# SCORCH.net
KiCad netlist of a schematic drawn in EAGLE
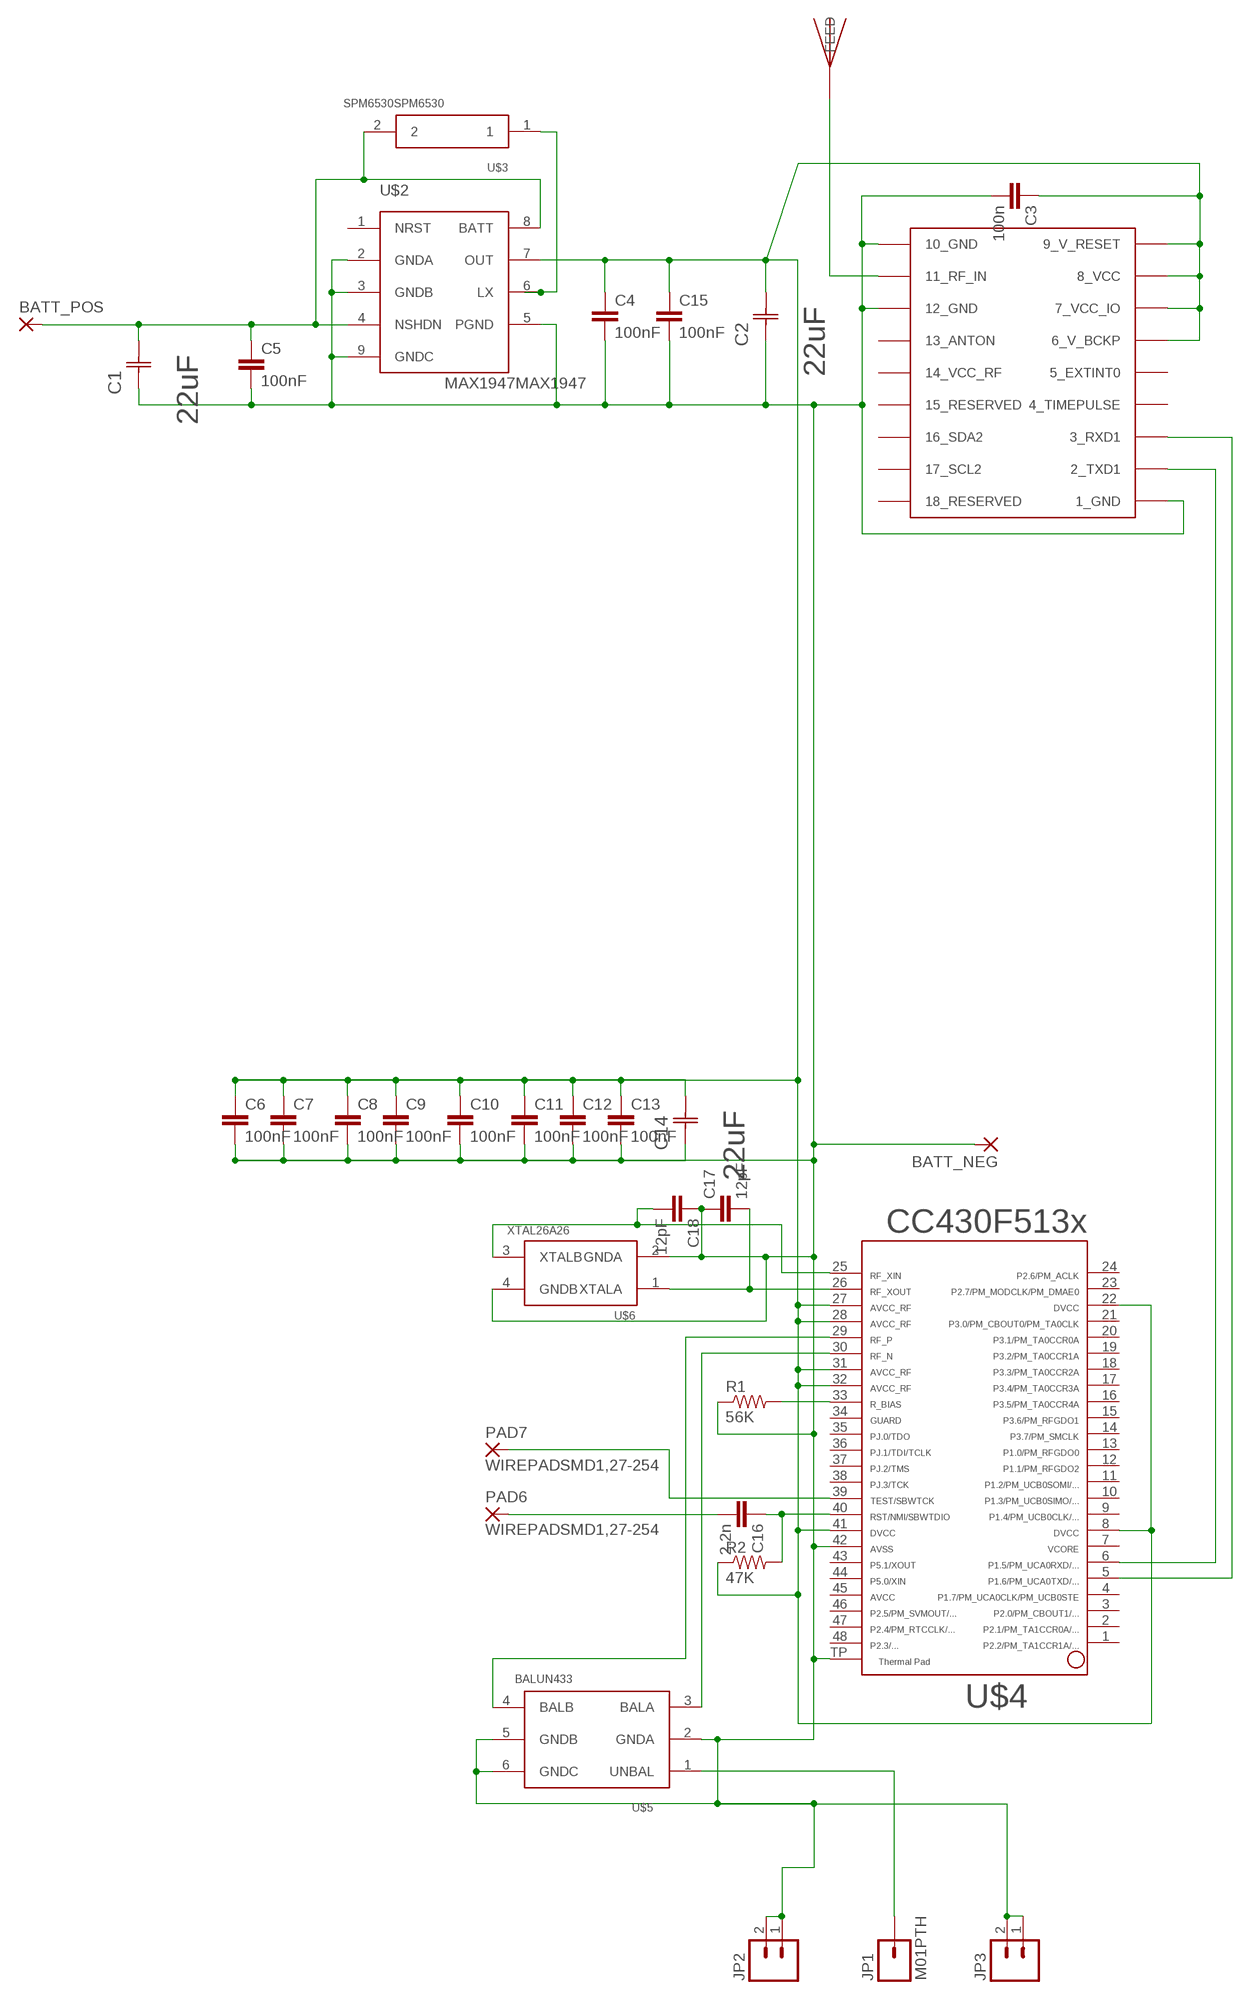
[diagram p0: schematic, sheet 1]

(export (version "E")
  (design (tool "Eeschema 10.0.6"))
  (components
    (comp (ref "BATT_NEG")
      (value "SMD2")
      (footprint "eagle-import:SMD1,27-2,54")
      (libsource (lib "eagle-import") (part "SMD2"))
    )
    (comp (ref "BATT_POS")
      (value "SMD2")
      (footprint "eagle-import:SMD1,27-2,54")
      (libsource (lib "eagle-import") (part "SMD2"))
    )
    (comp (ref "C1")
      (value "22uF")
      (footprint "eagle-import:CAPC2013X90N")
      (fields (field (name "MPN") "U0805R102KCT") (field (name "TOLERANCE") "±10%"))
      (libsource (lib "eagle-import") (part "U0805R102KCT"))
    )
    (comp (ref "C2")
      (value "22uF")
      (footprint "eagle-import:CAPC2013X90N")
      (fields (field (name "MPN") "U0805R102KCT") (field (name "TOLERANCE") "±10%"))
      (libsource (lib "eagle-import") (part "U0805R102KCT"))
    )
    (comp (ref "C3")
      (value "100n")
      (footprint "eagle-import:0402-CAP")
      (libsource (lib "eagle-import") (part "CAP0402-CAP"))
    )
    (comp (ref "C4")
      (value "100nF")
      (footprint "eagle-import:0402-CAP")
      (libsource (lib "eagle-import") (part "CAP0402-CAP"))
    )
    (comp (ref "C5")
      (value "100nF")
      (footprint "eagle-import:0402-CAP")
      (libsource (lib "eagle-import") (part "CAP0402-CAP"))
    )
    (comp (ref "C6")
      (value "100nF")
      (footprint "eagle-import:0402-CAP")
      (libsource (lib "eagle-import") (part "CAP0402-CAP"))
    )
    (comp (ref "C7")
      (value "100nF")
      (footprint "eagle-import:0402-CAP")
      (libsource (lib "eagle-import") (part "CAP0402-CAP"))
    )
    (comp (ref "C8")
      (value "100nF")
      (footprint "eagle-import:0402-CAP")
      (libsource (lib "eagle-import") (part "CAP0402-CAP"))
    )
    (comp (ref "C9")
      (value "100nF")
      (footprint "eagle-import:0402-CAP")
      (libsource (lib "eagle-import") (part "CAP0402-CAP"))
    )
    (comp (ref "C10")
      (value "100nF")
      (footprint "eagle-import:0402-CAP")
      (libsource (lib "eagle-import") (part "CAP0402-CAP"))
    )
    (comp (ref "C11")
      (value "100nF")
      (footprint "eagle-import:0402-CAP")
      (libsource (lib "eagle-import") (part "CAP0402-CAP"))
    )
    (comp (ref "C12")
      (value "100nF")
      (footprint "eagle-import:0402-CAP")
      (libsource (lib "eagle-import") (part "CAP0402-CAP"))
    )
    (comp (ref "C13")
      (value "100nF")
      (footprint "eagle-import:0402-CAP")
      (libsource (lib "eagle-import") (part "CAP0402-CAP"))
    )
    (comp (ref "C14")
      (value "22uF")
      (footprint "eagle-import:CAPC2013X90N")
      (fields (field (name "MPN") "U0805R102KCT") (field (name "TOLERANCE") "±10%"))
      (libsource (lib "eagle-import") (part "U0805R102KCT"))
    )
    (comp (ref "C15")
      (value "100nF")
      (footprint "eagle-import:0402-CAP")
      (libsource (lib "eagle-import") (part "CAP0402-CAP"))
    )
    (comp (ref "C16")
      (value "2.2n")
      (footprint "eagle-import:0402-CAP")
      (libsource (lib "eagle-import") (part "CAP0402-CAP"))
    )
    (comp (ref "C17")
      (value "12pF")
      (footprint "eagle-import:0402-CAP")
      (libsource (lib "eagle-import") (part "CAP0402-CAP"))
    )
    (comp (ref "C18")
      (value "12pF")
      (footprint "eagle-import:0402-CAP")
      (libsource (lib "eagle-import") (part "CAP0402-CAP"))
    )
    (comp (ref "JP1")
      (value "M01PTH")
      (footprint "eagle-import:1X01")
      (libsource (lib "eagle-import") (part "M01PTH"))
    )
    (comp (ref "JP2")
      (value "M02PTH")
      (footprint "eagle-import:1X02")
      (libsource (lib "eagle-import") (part "M02PTH"))
    )
    (comp (ref "JP3")
      (value "M02PTH")
      (footprint "eagle-import:1X02")
      (libsource (lib "eagle-import") (part "M02PTH"))
    )
    (comp (ref "PAD6")
      (value "WIREPADSMD1,27-254")
      (footprint "eagle-import:SMD1,27-2,54")
      (libsource (lib "eagle-import") (part "WIREPADSMD1,27-254"))
    )
    (comp (ref "PAD7")
      (value "WIREPADSMD1,27-254")
      (footprint "eagle-import:SMD1,27-2,54")
      (libsource (lib "eagle-import") (part "WIREPADSMD1,27-254"))
    )
    (comp (ref "R1")
      (value "56K")
      (footprint "eagle-import:0603-RES")
      (libsource (lib "eagle-import") (part "RESISTOR0603-RES"))
    )
    (comp (ref "R2")
      (value "47K")
      (footprint "eagle-import:0603-RES")
      (libsource (lib "eagle-import") (part "RESISTOR0603-RES"))
    )
    (comp (ref "U$1")
      (value "UBLOX_MAX-6")
      (footprint "eagle-import:UBLOX_MAX-6")
      (libsource (lib "eagle-import") (part "UBLOX_MAX-6"))
    )
    (comp (ref "U$2")
      (value "MAX1947MAX1947")
      (footprint "eagle-import:8QFN")
      (libsource (lib "eagle-import") (part "MAX1947MAX1947"))
    )
    (comp (ref "U$3")
      (value "SPM6530SPM6530")
      (footprint "eagle-import:INDUCTOR")
      (libsource (lib "eagle-import") (part "SPM6530SPM6530"))
    )
    (comp (ref "U$4")
      (value "CC430F513X---RGZ48")
      (footprint "eagle-import:RGZ48")
      (libsource (lib "eagle-import") (part "CC430F513X---RGZ48"))
    )
    (comp (ref "U$5")
      (value "BALUN433")
      (footprint "eagle-import:BALUN")
      (libsource (lib "eagle-import") (part "BALUN433"))
    )
    (comp (ref "U$6")
      (value "XTAL26A26")
      (footprint "eagle-import:XTAL26")
      (libsource (lib "eagle-import") (part "XTAL26A26"))
    )
    (comp (ref "U$7")
      (value "JTI_ANTENNA-1575AT43A40")
      (footprint "eagle-import:JTI_ANTENNA-1575AT43A40")
      (libsource (lib "eagle-import") (part "JTI_ANTENNA-1575AT43A40"))
    )
  )
  (nets
    (net (code "1") (name "/7") (class "Default")
      (node (ref "U$4") (pin "7") (pinfunction "7_7") (pintype "power_in"))
    )
    (net (code "2") (name "/34") (class "Default")
      (node (ref "U$4") (pin "34") (pinfunction "34_34") (pintype "power_in"))
    )
    (net (code "3") (name "Net-(BATT_NEG-P)") (class "Default")
      (node (ref "BATT_NEG") (pin "1") (pinfunction "P_1") (pintype "passive"))
      (node (ref "C1") (pin "1") (pinfunction "C1_1") (pintype "passive"))
      (node (ref "C10") (pin "2") (pinfunction "2_2") (pintype "passive"))
      (node (ref "C11") (pin "2") (pinfunction "2_2") (pintype "passive"))
      (node (ref "C12") (pin "2") (pinfunction "2_2") (pintype "passive"))
      (node (ref "C13") (pin "2") (pinfunction "2_2") (pintype "passive"))
      (node (ref "C14") (pin "1") (pinfunction "C1_1") (pintype "passive"))
      (node (ref "C15") (pin "2") (pinfunction "2_2") (pintype "passive"))
      (node (ref "C17") (pin "1") (pinfunction "1_1") (pintype "passive"))
      (node (ref "C18") (pin "1") (pinfunction "1_1") (pintype "passive"))
      (node (ref "C2") (pin "1") (pinfunction "C1_1") (pintype "passive"))
      (node (ref "C3") (pin "2") (pinfunction "2_2") (pintype "passive"))
      (node (ref "C4") (pin "2") (pinfunction "2_2") (pintype "passive"))
      (node (ref "C5") (pin "2") (pinfunction "2_2") (pintype "passive"))
      (node (ref "C6") (pin "2") (pinfunction "2_2") (pintype "passive"))
      (node (ref "C7") (pin "2") (pinfunction "2_2") (pintype "passive"))
      (node (ref "C8") (pin "2") (pinfunction "2_2") (pintype "passive"))
      (node (ref "C9") (pin "2") (pinfunction "2_2") (pintype "passive"))
      (node (ref "JP2") (pin "1") (pinfunction "1_1") (pintype "passive"))
      (node (ref "JP2") (pin "2") (pinfunction "2_2") (pintype "passive"))
      (node (ref "JP3") (pin "1") (pinfunction "1_1") (pintype "passive"))
      (node (ref "JP3") (pin "2") (pinfunction "2_2") (pintype "passive"))
      (node (ref "R1") (pin "1") (pinfunction "1_1") (pintype "passive"))
      (node (ref "U$1") (pin "10_GND") (pinfunction "10_GND_10_GND") (pintype "power_in"))
      (node (ref "U$1") (pin "12_GND") (pinfunction "12_GND_12_GND") (pintype "power_in"))
      (node (ref "U$1") (pin "1_GND") (pinfunction "1_GND_1_GND") (pintype "power_in"))
      (node (ref "U$2") (pin "2") (pinfunction "GNDA_2") (pintype "bidirectional"))
      (node (ref "U$2") (pin "3") (pinfunction "GNDB_3") (pintype "bidirectional"))
      (node (ref "U$2") (pin "5") (pinfunction "PGND_5") (pintype "bidirectional"))
      (node (ref "U$2") (pin "9") (pinfunction "GNDC_9") (pintype "bidirectional"))
      (node (ref "U$4") (pin "42") (pinfunction "42_42") (pintype "power_in"))
      (node (ref "U$4") (pin "TP") (pinfunction "49_TP") (pintype "power_in"))
      (node (ref "U$5") (pin "2") (pinfunction "GNDA_2") (pintype "bidirectional"))
      (node (ref "U$5") (pin "5") (pinfunction "GNDB_5") (pintype "bidirectional"))
      (node (ref "U$5") (pin "6") (pinfunction "GNDC_6") (pintype "bidirectional"))
      (node (ref "U$6") (pin "2") (pinfunction "GNDA_2") (pintype "bidirectional"))
      (node (ref "U$6") (pin "4") (pinfunction "GNDB_4") (pintype "bidirectional"))
    )
    (net (code "4") (name "Net-(BATT_POS-P)") (class "Default")
      (node (ref "BATT_POS") (pin "1") (pinfunction "P_1") (pintype "passive"))
      (node (ref "C1") (pin "2") (pinfunction "C2_2") (pintype "passive"))
      (node (ref "C5") (pin "1") (pinfunction "1_1") (pintype "passive"))
      (node (ref "U$2") (pin "4") (pinfunction "NSHDN_4") (pintype "bidirectional"))
      (node (ref "U$2") (pin "8") (pinfunction "BATT_8") (pintype "bidirectional"))
      (node (ref "U$3") (pin "2") (pinfunction "2_2") (pintype "bidirectional"))
    )
    (net (code "5") (name "Net-(C14-C2)") (class "Default")
      (node (ref "C10") (pin "1") (pinfunction "1_1") (pintype "passive"))
      (node (ref "C11") (pin "1") (pinfunction "1_1") (pintype "passive"))
      (node (ref "C12") (pin "1") (pinfunction "1_1") (pintype "passive"))
      (node (ref "C13") (pin "1") (pinfunction "1_1") (pintype "passive"))
      (node (ref "C14") (pin "2") (pinfunction "C2_2") (pintype "passive"))
      (node (ref "C15") (pin "1") (pinfunction "1_1") (pintype "passive"))
      (node (ref "C2") (pin "2") (pinfunction "C2_2") (pintype "passive"))
      (node (ref "C3") (pin "1") (pinfunction "1_1") (pintype "passive"))
      (node (ref "C4") (pin "1") (pinfunction "1_1") (pintype "passive"))
      (node (ref "C6") (pin "1") (pinfunction "1_1") (pintype "passive"))
      (node (ref "C7") (pin "1") (pinfunction "1_1") (pintype "passive"))
      (node (ref "C8") (pin "1") (pinfunction "1_1") (pintype "passive"))
      (node (ref "C9") (pin "1") (pinfunction "1_1") (pintype "passive"))
      (node (ref "R2") (pin "1") (pinfunction "1_1") (pintype "passive"))
      (node (ref "U$1") (pin "6_V_BCKP") (pinfunction "6_V_BCKP_6_V_BCKP") (pintype "bidirectional"))
      (node (ref "U$1") (pin "7_VCC_IO") (pinfunction "7_VCC_IO_7_VCC_IO") (pintype "power_in"))
      (node (ref "U$1") (pin "8_VCC") (pinfunction "8_VCC_8_VCC") (pintype "power_in"))
      (node (ref "U$1") (pin "9_V_RESET") (pinfunction "9_V_RESET_9_V_RESET") (pintype "power_in"))
      (node (ref "U$2") (pin "7") (pinfunction "OUT_7") (pintype "bidirectional"))
      (node (ref "U$4") (pin "22") (pinfunction "22_22") (pintype "power_in"))
      (node (ref "U$4") (pin "27") (pinfunction "27_27") (pintype "power_in"))
      (node (ref "U$4") (pin "28") (pinfunction "28_28") (pintype "bidirectional"))
      (node (ref "U$4") (pin "31") (pinfunction "31_31") (pintype "power_in"))
      (node (ref "U$4") (pin "32") (pinfunction "32_32") (pintype "power_in"))
      (node (ref "U$4") (pin "41") (pinfunction "41_41") (pintype "power_in"))
      (node (ref "U$4") (pin "8") (pinfunction "8_8") (pintype "power_in"))
    )
    (net (code "6") (name "Net-(C16-Pad1)") (class "Default")
      (node (ref "C16") (pin "1") (pinfunction "1_1") (pintype "passive"))
      (node (ref "R2") (pin "2") (pinfunction "2_2") (pintype "passive"))
      (node (ref "U$4") (pin "40") (pinfunction "40_40") (pintype "bidirectional"))
    )
    (net (code "7") (name "Net-(PAD6-P)") (class "Default")
      (node (ref "C16") (pin "2") (pinfunction "2_2") (pintype "passive"))
      (node (ref "PAD6") (pin "1") (pinfunction "P_1") (pintype "passive"))
    )
    (net (code "8") (name "Net-(PAD7-P)") (class "Default")
      (node (ref "PAD7") (pin "1") (pinfunction "P_1") (pintype "passive"))
      (node (ref "U$4") (pin "39") (pinfunction "39_39") (pintype "input"))
    )
    (net (code "9") (name "Net-(R1-Pad2)") (class "Default")
      (node (ref "R1") (pin "2") (pinfunction "2_2") (pintype "passive"))
      (node (ref "U$4") (pin "33") (pinfunction "33_33") (pintype "power_in"))
    )
    (net (code "10") (name "Net-(U$1-Pad2_TXD1)") (class "Default")
      (node (ref "U$1") (pin "2_TXD1") (pinfunction "2_TXD1_2_TXD1") (pintype "bidirectional"))
      (node (ref "U$4") (pin "6") (pinfunction "6_6") (pintype "bidirectional"))
    )
    (net (code "11") (name "Net-(U$1-Pad3_RXD1)") (class "Default")
      (node (ref "U$1") (pin "3_RXD1") (pinfunction "3_RXD1_3_RXD1") (pintype "bidirectional"))
      (node (ref "U$4") (pin "5") (pinfunction "5_5") (pintype "bidirectional"))
    )
    (net (code "12") (name "Net-(U$1-Pad11_RF_IN)") (class "Default")
      (node (ref "U$1") (pin "11_RF_IN") (pinfunction "11_RF_IN_11_RF_IN") (pintype "bidirectional"))
      (node (ref "U$7") (pin "FEED") (pinfunction "FEED_FEED") (pintype "bidirectional"))
    )
    (net (code "13") (name "Net-(U$2-LX)") (class "Default")
      (node (ref "U$2") (pin "6") (pinfunction "LX_6") (pintype "bidirectional"))
      (node (ref "U$3") (pin "1") (pinfunction "1_1") (pintype "bidirectional"))
    )
    (net (code "14") (name "Net-(U$5-BALA)") (class "Default")
      (node (ref "U$4") (pin "30") (pinfunction "30_30") (pintype "bidirectional"))
      (node (ref "U$5") (pin "3") (pinfunction "BALA_3") (pintype "bidirectional"))
    )
    (net (code "15") (name "Net-(U$5-BALB)") (class "Default")
      (node (ref "U$4") (pin "29") (pinfunction "29_29") (pintype "bidirectional"))
      (node (ref "U$5") (pin "4") (pinfunction "BALB_4") (pintype "bidirectional"))
    )
    (net (code "16") (name "Net-(U$5-UNBAL)") (class "Default")
      (node (ref "JP1") (pin "1") (pinfunction "1_1") (pintype "passive"))
      (node (ref "U$5") (pin "1") (pinfunction "UNBAL_1") (pintype "bidirectional"))
    )
    (net (code "17") (name "Net-(U$6-XTALA)") (class "Default")
      (node (ref "C17") (pin "2") (pinfunction "2_2") (pintype "passive"))
      (node (ref "U$4") (pin "26") (pinfunction "26_26") (pintype "output"))
      (node (ref "U$6") (pin "1") (pinfunction "XTALA_1") (pintype "bidirectional"))
    )
    (net (code "18") (name "Net-(U$6-XTALB)") (class "Default")
      (node (ref "C18") (pin "2") (pinfunction "2_2") (pintype "passive"))
      (node (ref "U$4") (pin "25") (pinfunction "25_25") (pintype "input"))
      (node (ref "U$6") (pin "3") (pinfunction "XTALB_3") (pintype "bidirectional"))
    )
    (net (code "19") (name "unconnected-(U$1-Pad4_TIMEPULSE)") (class "Default")
      (node (ref "U$1") (pin "4_TIMEPULSE") (pinfunction "4_TIMEPULSE_4_TIMEPULSE") (pintype "bidirectional"))
    )
    (net (code "20") (name "unconnected-(U$1-Pad5_EXTINT0)") (class "Default")
      (node (ref "U$1") (pin "5_EXTINT0") (pinfunction "5_EXTINT0_5_EXTINT0") (pintype "bidirectional"))
    )
    (net (code "21") (name "unconnected-(U$1-Pad13_ANTON)") (class "Default")
      (node (ref "U$1") (pin "13_ANTON") (pinfunction "13_ANTON_13_ANTON") (pintype "bidirectional"))
    )
    (net (code "22") (name "unconnected-(U$1-Pad14_VCC_RF)") (class "Default")
      (node (ref "U$1") (pin "14_VCC_RF") (pinfunction "14_VCC_RF_14_VCC_RF") (pintype "bidirectional"))
    )
    (net (code "23") (name "unconnected-(U$1-Pad15_RESERVED)") (class "Default")
      (node (ref "U$1") (pin "15_RESERVED") (pinfunction "15_RESERVED_15_RESERVED") (pintype "bidirectional"))
    )
    (net (code "24") (name "unconnected-(U$1-Pad16_SDA2)") (class "Default")
      (node (ref "U$1") (pin "16_SDA2") (pinfunction "16_SDA2_16_SDA2") (pintype "bidirectional"))
    )
    (net (code "25") (name "unconnected-(U$1-Pad17_SCL2)") (class "Default")
      (node (ref "U$1") (pin "17_SCL2") (pinfunction "17_SCL2_17_SCL2") (pintype "bidirectional"))
    )
    (net (code "26") (name "unconnected-(U$1-Pad18_RESERVED)") (class "Default")
      (node (ref "U$1") (pin "18_RESERVED") (pinfunction "18_RESERVED_18_RESERVED") (pintype "bidirectional"))
    )
    (net (code "27") (name "unconnected-(U$2-NRST-Pad1)") (class "Default")
      (node (ref "U$2") (pin "1") (pinfunction "NRST_1") (pintype "bidirectional"))
    )
    (net (code "28") (name "unconnected-(U$4-Pad1)") (class "Default")
      (node (ref "U$4") (pin "1") (pinfunction "1_1") (pintype "bidirectional"))
    )
    (net (code "29") (name "unconnected-(U$4-Pad2)") (class "Default")
      (node (ref "U$4") (pin "2") (pinfunction "2_2") (pintype "bidirectional"))
    )
    (net (code "30") (name "unconnected-(U$4-Pad3)") (class "Default")
      (node (ref "U$4") (pin "3") (pinfunction "3_3") (pintype "bidirectional"))
    )
    (net (code "31") (name "unconnected-(U$4-Pad4)") (class "Default")
      (node (ref "U$4") (pin "4") (pinfunction "4_4") (pintype "bidirectional"))
    )
    (net (code "32") (name "unconnected-(U$4-Pad9)") (class "Default")
      (node (ref "U$4") (pin "9") (pinfunction "9_9") (pintype "bidirectional"))
    )
    (net (code "33") (name "unconnected-(U$4-Pad10)") (class "Default")
      (node (ref "U$4") (pin "10") (pinfunction "10_10") (pintype "bidirectional"))
    )
    (net (code "34") (name "unconnected-(U$4-Pad11)") (class "Default")
      (node (ref "U$4") (pin "11") (pinfunction "11_11") (pintype "bidirectional"))
    )
    (net (code "35") (name "unconnected-(U$4-Pad12)") (class "Default")
      (node (ref "U$4") (pin "12") (pinfunction "12_12") (pintype "bidirectional"))
    )
    (net (code "36") (name "unconnected-(U$4-Pad13)") (class "Default")
      (node (ref "U$4") (pin "13") (pinfunction "13_13") (pintype "bidirectional"))
    )
    (net (code "37") (name "unconnected-(U$4-Pad14)") (class "Default")
      (node (ref "U$4") (pin "14") (pinfunction "14_14") (pintype "bidirectional"))
    )
    (net (code "38") (name "unconnected-(U$4-Pad15)") (class "Default")
      (node (ref "U$4") (pin "15") (pinfunction "15_15") (pintype "bidirectional"))
    )
    (net (code "39") (name "unconnected-(U$4-Pad16)") (class "Default")
      (node (ref "U$4") (pin "16") (pinfunction "16_16") (pintype "bidirectional"))
    )
    (net (code "40") (name "unconnected-(U$4-Pad17)") (class "Default")
      (node (ref "U$4") (pin "17") (pinfunction "17_17") (pintype "bidirectional"))
    )
    (net (code "41") (name "unconnected-(U$4-Pad18)") (class "Default")
      (node (ref "U$4") (pin "18") (pinfunction "18_18") (pintype "bidirectional"))
    )
    (net (code "42") (name "unconnected-(U$4-Pad19)") (class "Default")
      (node (ref "U$4") (pin "19") (pinfunction "19_19") (pintype "bidirectional"))
    )
    (net (code "43") (name "unconnected-(U$4-Pad20)") (class "Default")
      (node (ref "U$4") (pin "20") (pinfunction "20_20") (pintype "bidirectional"))
    )
    (net (code "44") (name "unconnected-(U$4-Pad21)") (class "Default")
      (node (ref "U$4") (pin "21") (pinfunction "21_21") (pintype "bidirectional"))
    )
    (net (code "45") (name "unconnected-(U$4-Pad23)") (class "Default")
      (node (ref "U$4") (pin "23") (pinfunction "23_23") (pintype "bidirectional"))
    )
    (net (code "46") (name "unconnected-(U$4-Pad24)") (class "Default")
      (node (ref "U$4") (pin "24") (pinfunction "24_24") (pintype "bidirectional"))
    )
    (net (code "47") (name "unconnected-(U$4-Pad35)") (class "Default")
      (node (ref "U$4") (pin "35") (pinfunction "35_35") (pintype "bidirectional"))
    )
    (net (code "48") (name "unconnected-(U$4-Pad36)") (class "Default")
      (node (ref "U$4") (pin "36") (pinfunction "36_36") (pintype "bidirectional"))
    )
    (net (code "49") (name "unconnected-(U$4-Pad37)") (class "Default")
      (node (ref "U$4") (pin "37") (pinfunction "37_37") (pintype "bidirectional"))
    )
    (net (code "50") (name "unconnected-(U$4-Pad38)") (class "Default")
      (node (ref "U$4") (pin "38") (pinfunction "38_38") (pintype "bidirectional"))
    )
    (net (code "51") (name "unconnected-(U$4-Pad43)") (class "Default")
      (node (ref "U$4") (pin "43") (pinfunction "43_43") (pintype "input"))
    )
    (net (code "52") (name "unconnected-(U$4-Pad44)") (class "Default")
      (node (ref "U$4") (pin "44") (pinfunction "44_44") (pintype "input"))
    )
    (net (code "53") (name "unconnected-(U$4-Pad45)") (class "Default")
      (node (ref "U$4") (pin "45") (pinfunction "45_45") (pintype "input"))
    )
    (net (code "54") (name "unconnected-(U$4-Pad46)") (class "Default")
      (node (ref "U$4") (pin "46") (pinfunction "46_46") (pintype "bidirectional"))
    )
    (net (code "55") (name "unconnected-(U$4-Pad47)") (class "Default")
      (node (ref "U$4") (pin "47") (pinfunction "47_47") (pintype "input"))
    )
    (net (code "56") (name "unconnected-(U$4-Pad48)") (class "Default")
      (node (ref "U$4") (pin "48") (pinfunction "48_48") (pintype "bidirectional"))
    )
  )
)
